# NB-IoT-ideaboard-with-GPS-withnames.net
KiCad netlist of a schematic drawn in EAGLE
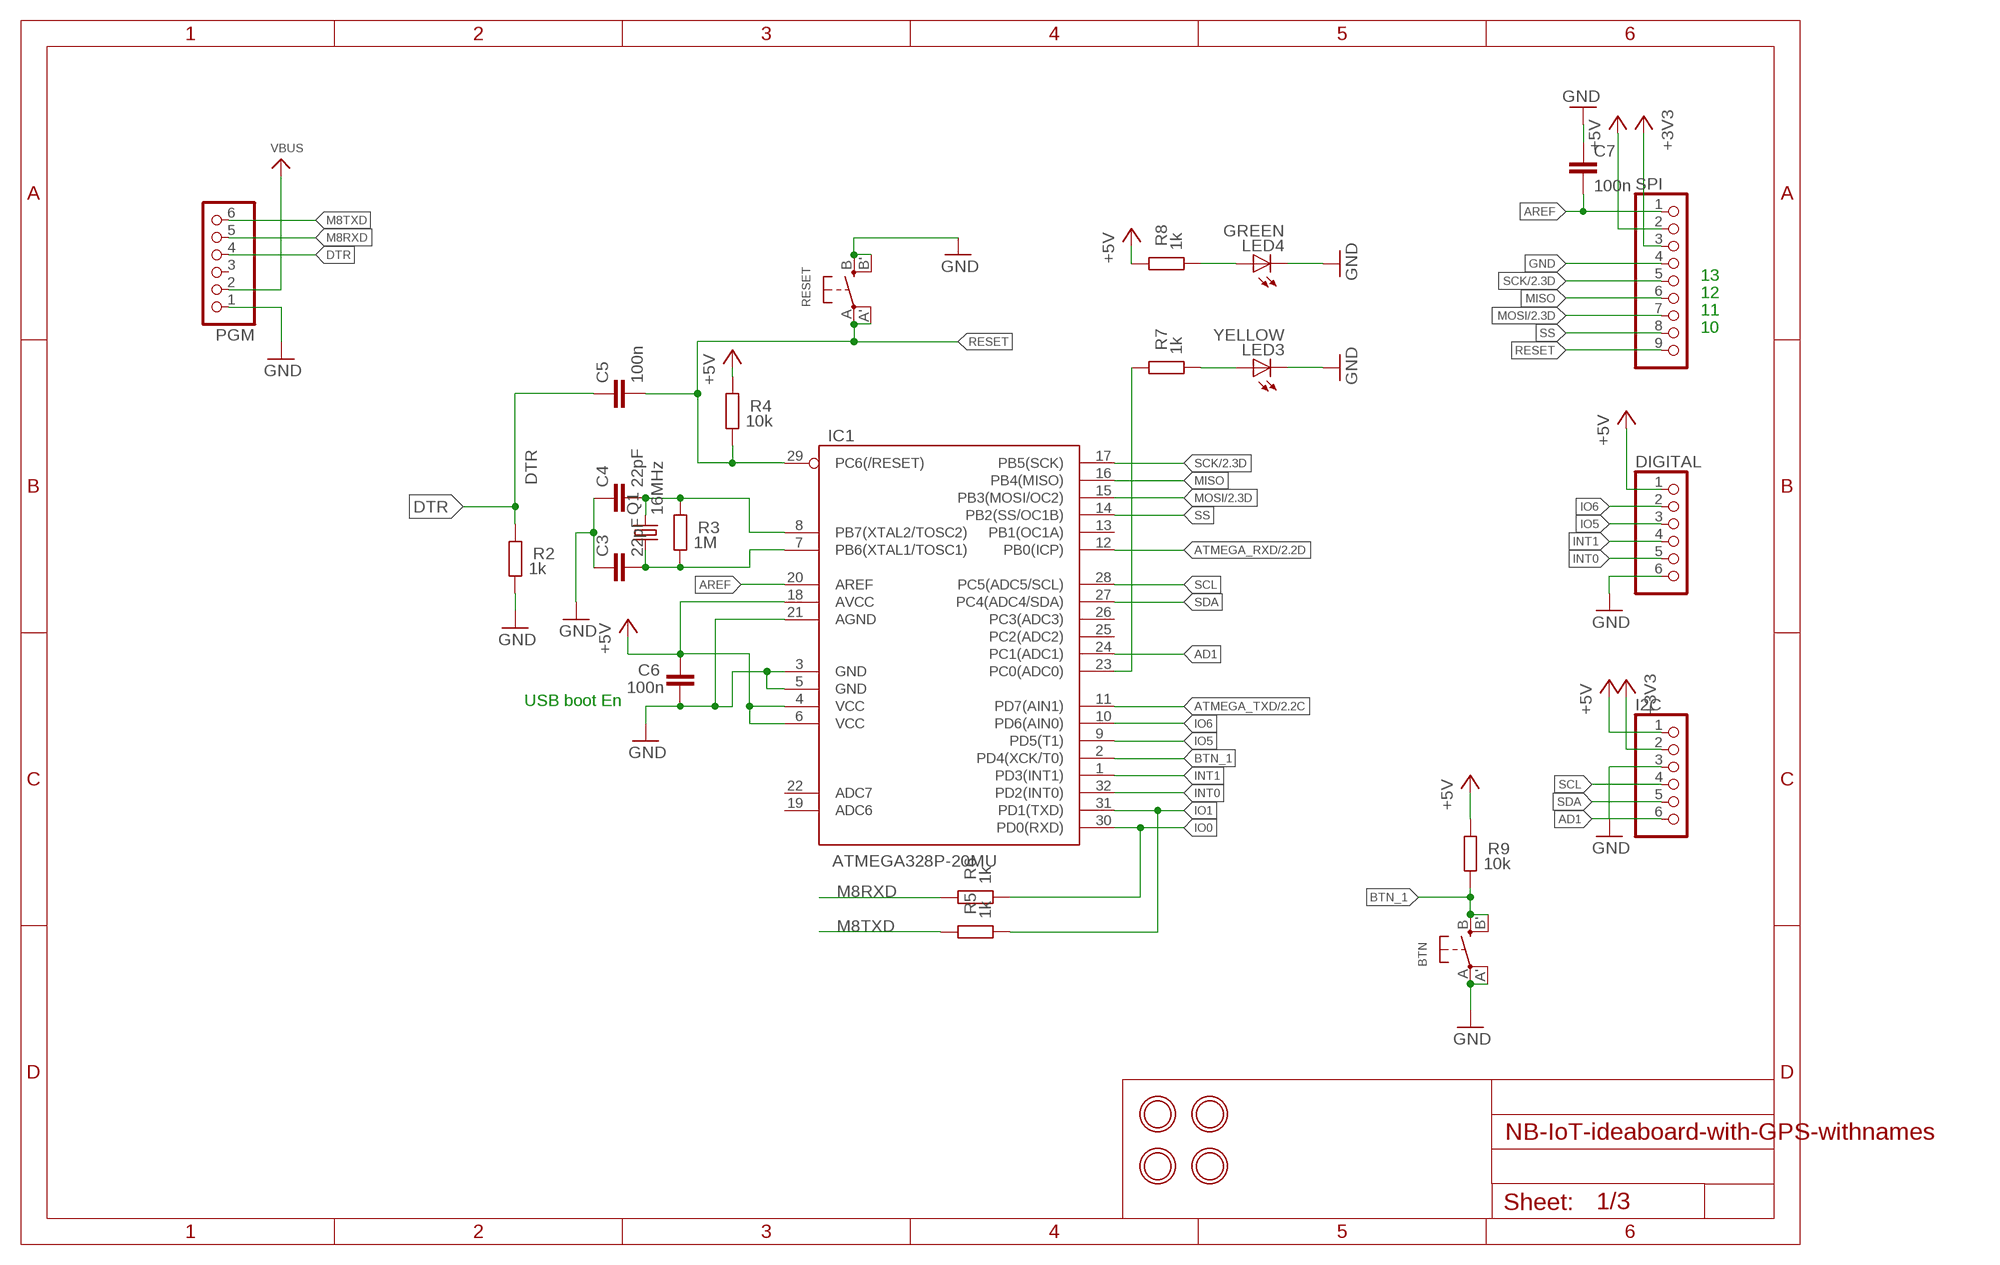
[diagram p0: schematic, sheet 1]
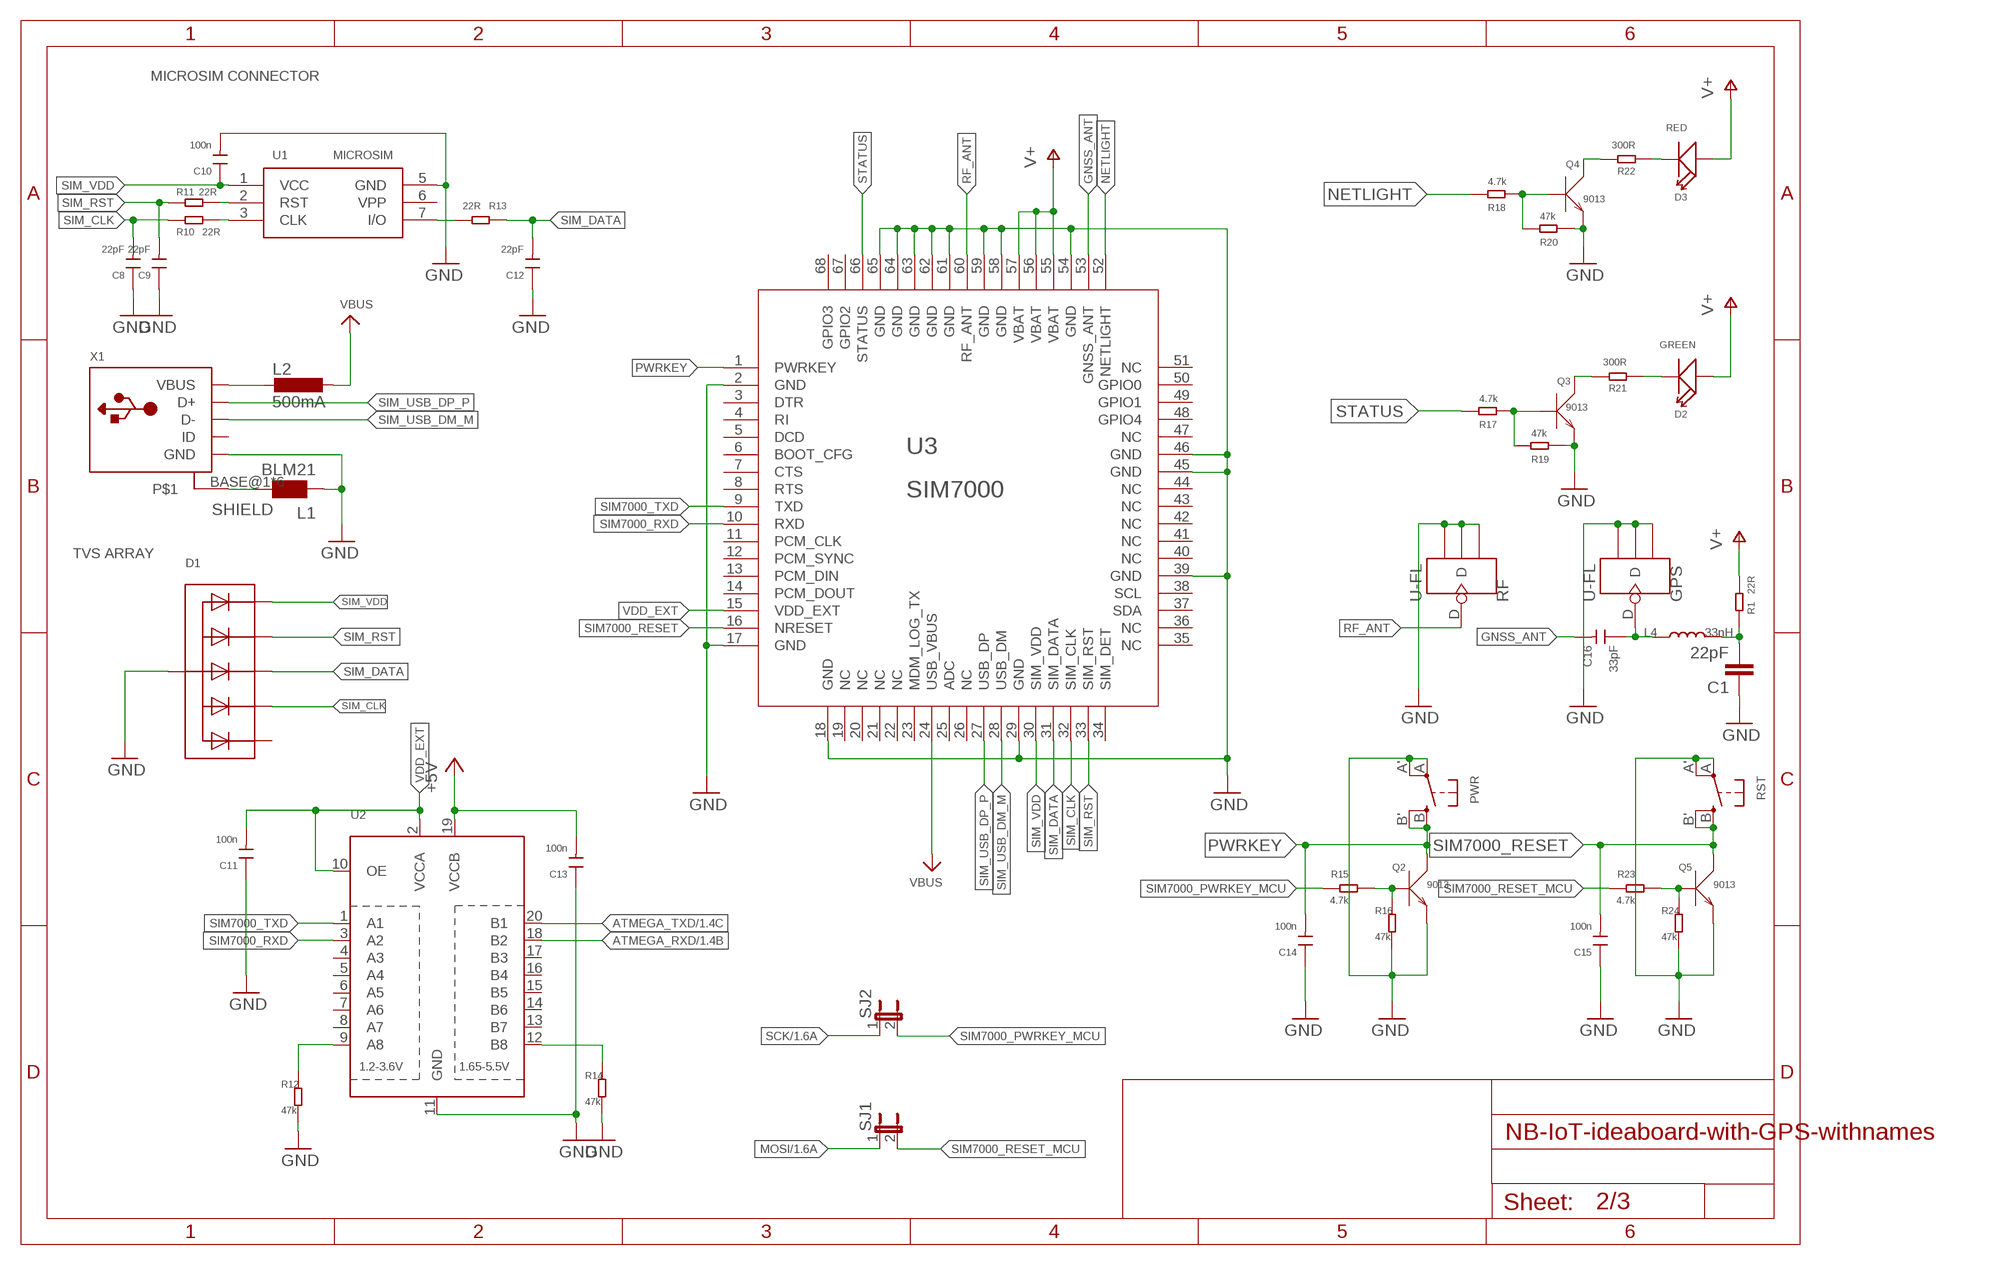
[diagram p1: schematic, sheet 2]
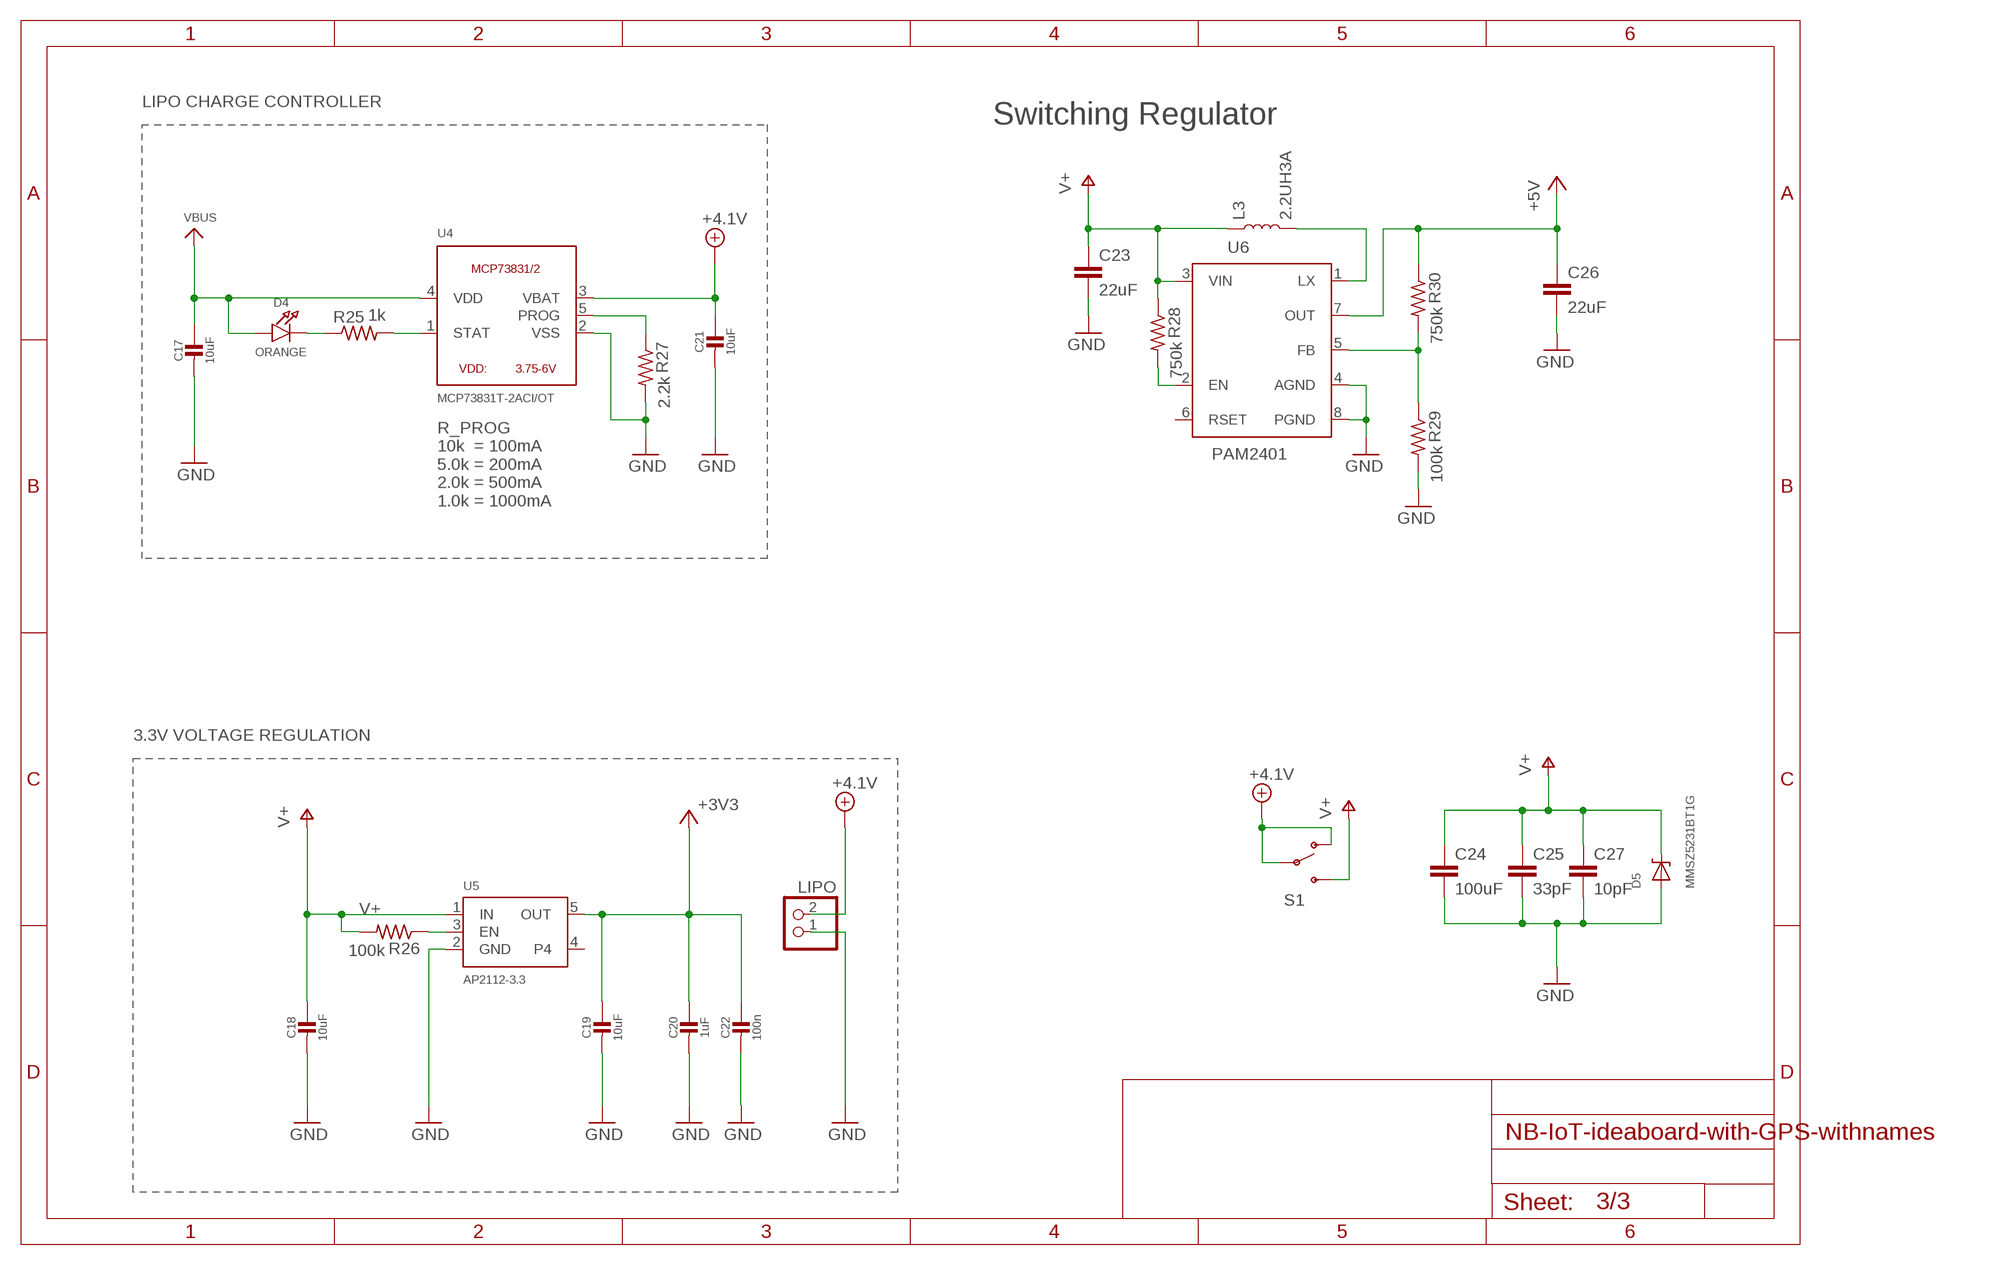
[diagram p2: schematic, sheet 3]

(export (version "E")
  (design (tool "Eeschema 10.0.6"))
  (components
    (comp (ref "C17")
      (value "10uF")
      (footprint "eagle-import:_0805")
      (libsource (lib "eagle-import") (part "CAP_CERAMIC_0805"))
    )
    (comp (ref "C18")
      (value "10uF")
      (footprint "eagle-import:_0805MP")
      (libsource (lib "eagle-import") (part "CAP_CERAMIC_0805MP"))
    )
    (comp (ref "C19")
      (value "10uF")
      (footprint "eagle-import:_0805MP")
      (libsource (lib "eagle-import") (part "CAP_CERAMIC_0805MP"))
    )
    (comp (ref "C20")
      (value "1uF")
      (footprint "eagle-import:_0805MP")
      (libsource (lib "eagle-import") (part "CAP_CERAMIC_0805MP"))
    )
    (comp (ref "C21")
      (value "10uF")
      (footprint "eagle-import:_0805")
      (libsource (lib "eagle-import") (part "CAP_CERAMIC_0805"))
    )
    (comp (ref "C22")
      (value "100n")
      (footprint "eagle-import:_0805MP")
      (libsource (lib "eagle-import") (part "CAP_CERAMIC_0805MP"))
    )
    (comp (ref "C23")
      (value "22uF")
      (footprint "eagle-import:0805")
      (libsource (lib "eagle-import") (part "22UF-0805-6.3V-20%"))
    )
    (comp (ref "C24")
      (value "100uF")
      (footprint "eagle-import:1210")
      (libsource (lib "eagle-import") (part "22UF-1210-16V-20%"))
    )
    (comp (ref "C25")
      (value "33pF")
      (footprint "eagle-import:0805")
      (libsource (lib "eagle-import") (part "22UF-0805-6.3V-20%"))
    )
    (comp (ref "C26")
      (value "22uF")
      (footprint "eagle-import:0805")
      (libsource (lib "eagle-import") (part "22UF-0805-6.3V-20%"))
    )
    (comp (ref "C27")
      (value "10pF")
      (footprint "eagle-import:0805")
      (libsource (lib "eagle-import") (part "22UF-0805-6.3V-20%"))
    )
    (comp (ref "D4")
      (value "ORANGE")
      (footprint "eagle-import:CHIPLED_0805")
      (libsource (lib "eagle-import") (part "LED0805"))
    )
    (comp (ref "D5")
      (value "MMSZ5231BT1G")
      (footprint "eagle-import:SOD-123")
      (libsource (lib "eagle-import") (part "DIODE-ZENERSOD123"))
    )
    (comp (ref "L3")
      (value "2.2UH3A")
      (footprint "eagle-import:INDUCTOR_4X4MM")
      (libsource (lib "eagle-import") (part "INDUCTOR-IFSC1515AHER2R2M01"))
    )
    (comp (ref "LIPO")
      (value "JST_2PIN-SMT")
      (footprint "eagle-import:JST-PH-2-SMT")
      (libsource (lib "eagle-import") (part "JST_2PIN-SMT"))
    )
    (comp (ref "R25")
      (value "1k")
      (footprint "eagle-import:M0805")
      (libsource (lib "eagle-import") (part "R-US_M0805"))
    )
    (comp (ref "R26")
      (value "100k")
      (footprint "eagle-import:M0805")
      (libsource (lib "eagle-import") (part "R-US_M0805"))
    )
    (comp (ref "R27")
      (value "2.2k")
      (footprint "eagle-import:M0805")
      (libsource (lib "eagle-import") (part "R-US_M0805"))
    )
    (comp (ref "R28")
      (value "750k")
      (footprint "eagle-import:M0805")
      (libsource (lib "eagle-import") (part "R-US_M0805"))
    )
    (comp (ref "R29")
      (value "100k")
      (footprint "eagle-import:M0805")
      (libsource (lib "eagle-import") (part "R-US_M0805"))
    )
    (comp (ref "R30")
      (value "750k")
      (footprint "eagle-import:M0805")
      (libsource (lib "eagle-import") (part "R-US_M0805"))
    )
    (comp (ref "S1")
      (value "SWITCH-SPDT-SMD-A")
      (footprint "eagle-import:SWITCH-SPST-SMD-A")
      (libsource (lib "eagle-import") (part "SWITCH-SPDT-SMD-A"))
    )
    (comp (ref "U4")
      (value "MCP73831T-2ACI/OT")
      (footprint "eagle-import:SOT23-5")
      (libsource (lib "eagle-import") (part "MCP73831/2"))
    )
    (comp (ref "U5")
      (value "AP2112-3.3")
      (footprint "eagle-import:SOT23-5")
      (libsource (lib "eagle-import") (part "VREG_SOT23-5"))
    )
    (comp (ref "U6")
      (value "PAM2401")
      (footprint "eagle-import:MSOP8")
      (libsource (lib "eagle-import") (part "PAM2401"))
    )
    (comp (ref "$H1")
      (value "MOUNTINGHOLE3.0THIN")
      (footprint "eagle-import:MOUNTINGHOLE_3.0_PLATEDTHIN")
      (libsource (lib "eagle-import") (part "MOUNTINGHOLE3.0THIN"))
    )
    (comp (ref "$H2")
      (value "MOUNTINGHOLE3.0THIN")
      (footprint "eagle-import:MOUNTINGHOLE_3.0_PLATEDTHIN")
      (libsource (lib "eagle-import") (part "MOUNTINGHOLE3.0THIN"))
    )
    (comp (ref "$H3")
      (value "MOUNTINGHOLE3.0THIN")
      (footprint "eagle-import:MOUNTINGHOLE_3.0_PLATEDTHIN")
      (libsource (lib "eagle-import") (part "MOUNTINGHOLE3.0THIN"))
    )
    (comp (ref "$H4")
      (value "MOUNTINGHOLE3.0THIN")
      (footprint "eagle-import:MOUNTINGHOLE_3.0_PLATEDTHIN")
      (libsource (lib "eagle-import") (part "MOUNTINGHOLE3.0THIN"))
    )
    (comp (ref "BTN")
      (value "SWITCH_TACT_SMT4.6X2.8")
      (footprint "eagle-import:BTN_KMR2_4.6X2.8")
      (libsource (lib "eagle-import") (part "SWITCH_TACT_SMT4.6X2.8"))
    )
    (comp (ref "C3")
      (value "22pF")
      (footprint "eagle-import:C0805")
      (libsource (lib "eagle-import") (part "C-EUC0805"))
    )
    (comp (ref "C4")
      (value "22pF")
      (footprint "eagle-import:C0805")
      (libsource (lib "eagle-import") (part "C-EUC0805"))
    )
    (comp (ref "C5")
      (value "100n")
      (footprint "eagle-import:C0805")
      (libsource (lib "eagle-import") (part "C-EUC0805"))
    )
    (comp (ref "C6")
      (value "100n")
      (footprint "eagle-import:C0805")
      (libsource (lib "eagle-import") (part "C-EUC0805"))
    )
    (comp (ref "C7")
      (value "100n")
      (footprint "eagle-import:C0805")
      (libsource (lib "eagle-import") (part "C-EUC0805"))
    )
    (comp (ref "DIGITAL")
      (value "PINHD-1X6")
      (footprint "eagle-import:1X06")
      (libsource (lib "eagle-import") (part "PINHD-1X6"))
    )
    (comp (ref "I2C")
      (value "PINHD-1X6")
      (footprint "eagle-import:1X06")
      (libsource (lib "eagle-import") (part "PINHD-1X6"))
    )
    (comp (ref "IC1")
      (value "ATMEGA328P-20MU")
      (footprint "eagle-import:TQFP32-08")
      (libsource (lib "eagle-import") (part "MEGA8-AI"))
    )
    (comp (ref "LED3")
      (value "YELLOW")
      (footprint "eagle-import:CHIP-LED0805")
      (libsource (lib "eagle-import") (part "LEDCHIP-LED0805"))
    )
    (comp (ref "LED4")
      (value "GREEN")
      (footprint "eagle-import:CHIP-LED0805")
      (libsource (lib "eagle-import") (part "LEDCHIP-LED0805"))
    )
    (comp (ref "PGM")
      (value "PINHD-1X6")
      (footprint "eagle-import:1X06")
      (libsource (lib "eagle-import") (part "PINHD-1X6"))
    )
    (comp (ref "Q1")
      (value "16MHz")
      (footprint "eagle-import:CTS406")
      (libsource (lib "eagle-import") (part "CRYSTALCTS406"))
    )
    (comp (ref "R2")
      (value "1k")
      (footprint "eagle-import:R0805")
      (libsource (lib "eagle-import") (part "R-EU_R0805"))
    )
    (comp (ref "R3")
      (value "1M")
      (footprint "eagle-import:R0805")
      (libsource (lib "eagle-import") (part "R-EU_R0805"))
    )
    (comp (ref "R4")
      (value "10k")
      (footprint "eagle-import:R0805")
      (libsource (lib "eagle-import") (part "R-EU_R0805"))
    )
    (comp (ref "R5")
      (value "1k")
      (footprint "eagle-import:R0805")
      (libsource (lib "eagle-import") (part "R-EU_R0805"))
    )
    (comp (ref "R6")
      (value "1k")
      (footprint "eagle-import:R0805")
      (libsource (lib "eagle-import") (part "R-EU_R0805"))
    )
    (comp (ref "R7")
      (value "1k")
      (footprint "eagle-import:R0805")
      (libsource (lib "eagle-import") (part "R-EU_R0805"))
    )
    (comp (ref "R8")
      (value "1k")
      (footprint "eagle-import:R0805")
      (libsource (lib "eagle-import") (part "R-EU_R0805"))
    )
    (comp (ref "R9")
      (value "10k")
      (footprint "eagle-import:R0805")
      (libsource (lib "eagle-import") (part "R-EU_R0805"))
    )
    (comp (ref "RESET")
      (value "SWITCH_TACT_SMT4.6X2.8")
      (footprint "eagle-import:BTN_KMR2_4.6X2.8")
      (libsource (lib "eagle-import") (part "SWITCH_TACT_SMT4.6X2.8"))
    )
    (comp (ref "SPI")
      (value "PINHD-1X9")
      (footprint "eagle-import:1X09")
      (libsource (lib "eagle-import") (part "PINHD-1X9"))
    )
    (comp (ref "C1")
      (value "22pF")
      (footprint "eagle-import:C0805")
      (libsource (lib "eagle-import") (part "C-EUC0805"))
    )
    (comp (ref "C8")
      (value "22pF")
      (footprint "eagle-import:0805")
      (libsource (lib "eagle-import") (part "C-0805"))
    )
    (comp (ref "C9")
      (value "22pF")
      (footprint "eagle-import:0805")
      (libsource (lib "eagle-import") (part "C-0805"))
    )
    (comp (ref "C10")
      (value "100n")
      (footprint "eagle-import:0805")
      (libsource (lib "eagle-import") (part "C-0805"))
    )
    (comp (ref "C11")
      (value "100n")
      (footprint "eagle-import:0805")
      (libsource (lib "eagle-import") (part "C-0805"))
    )
    (comp (ref "C12")
      (value "22pF")
      (footprint "eagle-import:0805")
      (libsource (lib "eagle-import") (part "C-0805"))
    )
    (comp (ref "C13")
      (value "100n")
      (footprint "eagle-import:0805")
      (libsource (lib "eagle-import") (part "C-0805"))
    )
    (comp (ref "C14")
      (value "100n")
      (footprint "eagle-import:0805")
      (libsource (lib "eagle-import") (part "C-0805"))
    )
    (comp (ref "C15")
      (value "100n")
      (footprint "eagle-import:0805")
      (libsource (lib "eagle-import") (part "C-0805"))
    )
    (comp (ref "C16")
      (value "33pF")
      (footprint "eagle-import:0805")
      (libsource (lib "eagle-import") (part "C-0805"))
    )
    (comp (ref "D1")
      (value "TVSARRAY_5LANE")
      (footprint "eagle-import:SOT363")
      (libsource (lib "eagle-import") (part "TVSARRAY_5LANE"))
    )
    (comp (ref "D2")
      (value "GREEN")
      (footprint "eagle-import:LED-0805")
      (libsource (lib "eagle-import") (part "LED'0805'"))
    )
    (comp (ref "D3")
      (value "RED")
      (footprint "eagle-import:LED-0805")
      (libsource (lib "eagle-import") (part "LED'0805'"))
    )
    (comp (ref "GPS")
      (value "U-FL")
      (footprint "eagle-import:4P-U-FL")
      (libsource (lib "eagle-import") (part "ANTENNA-U-FL"))
    )
    (comp (ref "L1")
      (value "BLM21")
      (footprint "eagle-import:0805")
      (libsource (lib "eagle-import") (part "WE-CBF_0805"))
    )
    (comp (ref "L2")
      (value "500mA")
      (footprint "eagle-import:L1812")
      (libsource (lib "eagle-import") (part "L-EUL1812"))
    )
    (comp (ref "L4")
      (value "33nH")
      (footprint "eagle-import:L0805")
      (libsource (lib "eagle-import") (part "L0805"))
    )
    (comp (ref "PWR")
      (value "SWITCH_TACT_SMT4.6X2.8")
      (footprint "eagle-import:BTN_KMR2_4.6X2.8")
      (libsource (lib "eagle-import") (part "SWITCH_TACT_SMT4.6X2.8"))
    )
    (comp (ref "Q2")
      (value "9013")
      (footprint "eagle-import:SOT23")
      (libsource (lib "eagle-import") (part "TRANSISTOR-NPN-SOT23"))
    )
    (comp (ref "Q3")
      (value "9013")
      (footprint "eagle-import:SOT23")
      (libsource (lib "eagle-import") (part "TRANSISTOR-NPN-SOT23"))
    )
    (comp (ref "Q4")
      (value "9013")
      (footprint "eagle-import:SOT23")
      (libsource (lib "eagle-import") (part "TRANSISTOR-NPN-SOT23"))
    )
    (comp (ref "Q5")
      (value "9013")
      (footprint "eagle-import:SOT23")
      (libsource (lib "eagle-import") (part "TRANSISTOR-NPN-SOT23"))
    )
    (comp (ref "R1")
      (value "22R")
      (footprint "eagle-import:0805")
      (libsource (lib "eagle-import") (part "R-0805"))
    )
    (comp (ref "R10")
      (value "22R")
      (footprint "eagle-import:0805")
      (libsource (lib "eagle-import") (part "R-0805"))
    )
    (comp (ref "R11")
      (value "22R")
      (footprint "eagle-import:0805")
      (libsource (lib "eagle-import") (part "R-0805"))
    )
    (comp (ref "R12")
      (value "47k")
      (footprint "eagle-import:0805")
      (libsource (lib "eagle-import") (part "R-0805"))
    )
    (comp (ref "R13")
      (value "22R")
      (footprint "eagle-import:0805")
      (libsource (lib "eagle-import") (part "R-0805"))
    )
    (comp (ref "R14")
      (value "47k")
      (footprint "eagle-import:0805")
      (libsource (lib "eagle-import") (part "R-0805"))
    )
    (comp (ref "R15")
      (value "4.7k")
      (footprint "eagle-import:0805")
      (libsource (lib "eagle-import") (part "R-0805"))
    )
    (comp (ref "R16")
      (value "47k")
      (footprint "eagle-import:0805")
      (libsource (lib "eagle-import") (part "R-0805"))
    )
    (comp (ref "R17")
      (value "4.7k")
      (footprint "eagle-import:0805")
      (libsource (lib "eagle-import") (part "R-0805"))
    )
    (comp (ref "R18")
      (value "4.7k")
      (footprint "eagle-import:0805")
      (libsource (lib "eagle-import") (part "R-0805"))
    )
    (comp (ref "R19")
      (value "47k")
      (footprint "eagle-import:0805")
      (libsource (lib "eagle-import") (part "R-0805"))
    )
    (comp (ref "R20")
      (value "47k")
      (footprint "eagle-import:0805")
      (libsource (lib "eagle-import") (part "R-0805"))
    )
    (comp (ref "R21")
      (value "300R")
      (footprint "eagle-import:0805")
      (libsource (lib "eagle-import") (part "R-0805"))
    )
    (comp (ref "R22")
      (value "300R")
      (footprint "eagle-import:0805")
      (libsource (lib "eagle-import") (part "R-0805"))
    )
    (comp (ref "R23")
      (value "4.7k")
      (footprint "eagle-import:0805")
      (libsource (lib "eagle-import") (part "R-0805"))
    )
    (comp (ref "R24")
      (value "47k")
      (footprint "eagle-import:0805")
      (libsource (lib "eagle-import") (part "R-0805"))
    )
    (comp (ref "RF")
      (value "U-FL")
      (footprint "eagle-import:4P-U-FL")
      (libsource (lib "eagle-import") (part "ANTENNA-U-FL"))
    )
    (comp (ref "RST")
      (value "SWITCH_TACT_SMT4.6X2.8")
      (footprint "eagle-import:BTN_KMR2_4.6X2.8")
      (libsource (lib "eagle-import") (part "SWITCH_TACT_SMT4.6X2.8"))
    )
    (comp (ref "SJ1")
      (value "SPARKFUN-PASSIVES_JUMPER-PTH-2-NC")
      (footprint "eagle-import:SPARKFUN-PASSIVES_PTH-JUMPER-NC_BOTTOM_NO_SILK")
      (libsource (lib "eagle-import") (part "SPARKFUN-PASSIVES_JUMPER-PTH-2-NC"))
    )
    (comp (ref "SJ2")
      (value "SPARKFUN-PASSIVES_JUMPER-PTH-2-NC")
      (footprint "eagle-import:SPARKFUN-PASSIVES_PTH-JUMPER-NC_BOTTOM_NO_SILK")
      (libsource (lib "eagle-import") (part "SPARKFUN-PASSIVES_JUMPER-PTH-2-NC"))
    )
    (comp (ref "U1")
      (value "MICROSIM")
      (footprint "eagle-import:MICROSIM")
      (libsource (lib "eagle-import") (part "MICROSIM"))
    )
    (comp (ref "U2")
      (value "TXB0108PWR")
      (footprint "eagle-import:TSSOP20")
      (libsource (lib "eagle-import") (part "TXB0108PWR"))
    )
    (comp (ref "U3")
      (value "SIM7000")
      (footprint "eagle-import:SIM7000")
      (libsource (lib "eagle-import") (part "SIM7000"))
    )
    (comp (ref "X1")
      (value "USB_MICRO_20329_V2")
      (footprint "eagle-import:4UCONN_20329_V2")
      (libsource (lib "eagle-import") (part "USB_MICRO_20329_V2"))
    )
  )
  (nets
    (net (code "1") (name "+3V3") (class "Default")
      (node (ref "C19") (pin "1") (pinfunction "1_1") (pintype "passive"))
      (node (ref "C20") (pin "1") (pinfunction "1_1") (pintype "passive"))
      (node (ref "C22") (pin "1") (pinfunction "1_1") (pintype "passive"))
      (node (ref "I2C") (pin "2") (pinfunction "2_2") (pintype "passive"))
      (node (ref "SPI") (pin "3") (pinfunction "3_3") (pintype "passive"))
      (node (ref "U5") (pin "5") (pinfunction "OUT_5") (pintype "power_in"))
    )
    (net (code "2") (name "+4.1V") (class "Default")
      (node (ref "C21") (pin "1") (pinfunction "1_1") (pintype "passive"))
      (node (ref "LIPO") (pin "2") (pinfunction "1_2") (pintype "passive"))
      (node (ref "S1") (pin "1") (pinfunction "O_1") (pintype "passive"))
      (node (ref "S1") (pin "2") (pinfunction "P_2") (pintype "passive"))
      (node (ref "U4") (pin "3") (pinfunction "VBAT_3") (pintype "power_in"))
    )
    (net (code "3") (name "+5V") (class "Default")
      (node (ref "C13") (pin "2") (pinfunction "2_2") (pintype "passive"))
      (node (ref "C26") (pin "1") (pinfunction "1_1") (pintype "passive"))
      (node (ref "C6") (pin "2") (pinfunction "2_2") (pintype "passive"))
      (node (ref "DIGITAL") (pin "1") (pinfunction "1_1") (pintype "passive"))
      (node (ref "I2C") (pin "1") (pinfunction "1_1") (pintype "passive"))
      (node (ref "IC1") (pin "18") (pinfunction "AVCC_18") (pintype "bidirectional"))
      (node (ref "IC1") (pin "4") (pinfunction "VCC_4") (pintype "bidirectional"))
      (node (ref "IC1") (pin "6") (pinfunction "VCC_6") (pintype "bidirectional"))
      (node (ref "R30") (pin "1") (pinfunction "1_1") (pintype "passive"))
      (node (ref "R4") (pin "2") (pinfunction "2_2") (pintype "passive"))
      (node (ref "R8") (pin "2") (pinfunction "2_2") (pintype "passive"))
      (node (ref "R9") (pin "2") (pinfunction "2_2") (pintype "passive"))
      (node (ref "SPI") (pin "2") (pinfunction "2_2") (pintype "passive"))
      (node (ref "U2") (pin "19") (pinfunction "VCCB_19") (pintype "bidirectional"))
      (node (ref "U6") (pin "7") (pinfunction "OUT_7") (pintype "bidirectional"))
    )
    (net (code "4") (name "AD1") (class "Default")
      (node (ref "I2C") (pin "6") (pinfunction "6_6") (pintype "passive"))
      (node (ref "IC1") (pin "24") (pinfunction "PC1(ADC1)_24") (pintype "bidirectional"))
    )
    (net (code "5") (name "AREF") (class "Default")
      (node (ref "C7") (pin "2") (pinfunction "2_2") (pintype "passive"))
      (node (ref "IC1") (pin "20") (pinfunction "AREF_20") (pintype "bidirectional"))
      (node (ref "SPI") (pin "1") (pinfunction "1_1") (pintype "passive"))
    )
    (net (code "6") (name "ATMEGA_RXD") (class "Default")
      (node (ref "IC1") (pin "12") (pinfunction "PB0(ICP)_12") (pintype "bidirectional"))
      (node (ref "U2") (pin "18") (pinfunction "B2_18") (pintype "bidirectional"))
    )
    (net (code "7") (name "ATMEGA_TXD") (class "Default")
      (node (ref "IC1") (pin "11") (pinfunction "PD7(AIN1)_11") (pintype "bidirectional"))
      (node (ref "U2") (pin "20") (pinfunction "B1_20") (pintype "bidirectional"))
    )
    (net (code "8") (name "BTN_1") (class "Default")
      (node (ref "BTN") (pin "B") (pinfunction "S_B") (pintype "passive"))
      (node (ref "BTN") (pin "B'") (pinfunction "S1_B'") (pintype "passive"))
      (node (ref "IC1") (pin "2") (pinfunction "PD4(XCK/T0)_2") (pintype "bidirectional"))
      (node (ref "R9") (pin "1") (pinfunction "1_1") (pintype "passive"))
    )
    (net (code "9") (name "DTR") (class "Default")
      (node (ref "C5") (pin "1") (pinfunction "1_1") (pintype "passive"))
      (node (ref "PGM") (pin "4") (pinfunction "4_4") (pintype "passive"))
      (node (ref "R2") (pin "2") (pinfunction "2_2") (pintype "passive"))
    )
    (net (code "10") (name "GND") (class "Default")
      (node (ref "BTN") (pin "A") (pinfunction "P_A") (pintype "passive"))
      (node (ref "BTN") (pin "A'") (pinfunction "P1_A'") (pintype "passive"))
      (node (ref "C1") (pin "1") (pinfunction "1_1") (pintype "passive"))
      (node (ref "C10") (pin "2") (pinfunction "2_2") (pintype "passive"))
      (node (ref "C11") (pin "1") (pinfunction "1_1") (pintype "passive"))
      (node (ref "C12") (pin "1") (pinfunction "1_1") (pintype "passive"))
      (node (ref "C13") (pin "1") (pinfunction "1_1") (pintype "passive"))
      (node (ref "C14") (pin "1") (pinfunction "1_1") (pintype "passive"))
      (node (ref "C15") (pin "1") (pinfunction "1_1") (pintype "passive"))
      (node (ref "C17") (pin "2") (pinfunction "2_2") (pintype "passive"))
      (node (ref "C18") (pin "2") (pinfunction "2_2") (pintype "passive"))
      (node (ref "C19") (pin "2") (pinfunction "2_2") (pintype "passive"))
      (node (ref "C20") (pin "2") (pinfunction "2_2") (pintype "passive"))
      (node (ref "C21") (pin "2") (pinfunction "2_2") (pintype "passive"))
      (node (ref "C22") (pin "2") (pinfunction "2_2") (pintype "passive"))
      (node (ref "C23") (pin "2") (pinfunction "2_2") (pintype "passive"))
      (node (ref "C24") (pin "2") (pinfunction "2_2") (pintype "passive"))
      (node (ref "C25") (pin "2") (pinfunction "2_2") (pintype "passive"))
      (node (ref "C26") (pin "2") (pinfunction "2_2") (pintype "passive"))
      (node (ref "C27") (pin "2") (pinfunction "2_2") (pintype "passive"))
      (node (ref "C3") (pin "1") (pinfunction "1_1") (pintype "passive"))
      (node (ref "C4") (pin "1") (pinfunction "1_1") (pintype "passive"))
      (node (ref "C6") (pin "1") (pinfunction "1_1") (pintype "passive"))
      (node (ref "C7") (pin "1") (pinfunction "1_1") (pintype "passive"))
      (node (ref "C8") (pin "1") (pinfunction "1_1") (pintype "passive"))
      (node (ref "C9") (pin "1") (pinfunction "1_1") (pintype "passive"))
      (node (ref "D1") (pin "2") (pinfunction "A_2") (pintype "passive"))
      (node (ref "D5") (pin "A") (pinfunction "A_A") (pintype "passive"))
      (node (ref "DIGITAL") (pin "6") (pinfunction "6_6") (pintype "passive"))
      (node (ref "GPS") (pin "GND1") (pinfunction "GND1_GND1") (pintype "bidirectional"))
      (node (ref "GPS") (pin "GND2") (pinfunction "GND2_GND2") (pintype "bidirectional"))
      (node (ref "GPS") (pin "GND3") (pinfunction "GND3_GND3") (pintype "bidirectional"))
      (node (ref "I2C") (pin "3") (pinfunction "3_3") (pintype "passive"))
      (node (ref "IC1") (pin "21") (pinfunction "AGND_21") (pintype "bidirectional"))
      (node (ref "IC1") (pin "3") (pinfunction "GND_3") (pintype "bidirectional"))
      (node (ref "IC1") (pin "5") (pinfunction "GND_5") (pintype "bidirectional"))
      (node (ref "L1") (pin "1") (pinfunction "1_1") (pintype "passive"))
      (node (ref "LED3") (pin "C") (pinfunction "C_C") (pintype "passive"))
      (node (ref "LED4") (pin "C") (pinfunction "C_C") (pintype "passive"))
      (node (ref "LIPO") (pin "1") (pinfunction "2_1") (pintype "passive"))
      (node (ref "PGM") (pin "1") (pinfunction "1_1") (pintype "passive"))
      (node (ref "PWR") (pin "A") (pinfunction "P_A") (pintype "passive"))
      (node (ref "PWR") (pin "A'") (pinfunction "P1_A'") (pintype "passive"))
      (node (ref "Q2") (pin "2") (pinfunction "E_2") (pintype "passive"))
      (node (ref "Q3") (pin "2") (pinfunction "E_2") (pintype "passive"))
      (node (ref "Q4") (pin "2") (pinfunction "E_2") (pintype "passive"))
      (node (ref "Q5") (pin "2") (pinfunction "E_2") (pintype "passive"))
      (node (ref "R12") (pin "2") (pinfunction "2_2") (pintype "passive"))
      (node (ref "R14") (pin "2") (pinfunction "2_2") (pintype "passive"))
      (node (ref "R16") (pin "2") (pinfunction "2_2") (pintype "passive"))
      (node (ref "R19") (pin "2") (pinfunction "2_2") (pintype "passive"))
      (node (ref "R2") (pin "1") (pinfunction "1_1") (pintype "passive"))
      (node (ref "R20") (pin "2") (pinfunction "2_2") (pintype "passive"))
      (node (ref "R24") (pin "2") (pinfunction "2_2") (pintype "passive"))
      (node (ref "R27") (pin "2") (pinfunction "2_2") (pintype "passive"))
      (node (ref "R29") (pin "2") (pinfunction "2_2") (pintype "passive"))
      (node (ref "RESET") (pin "B") (pinfunction "S_B") (pintype "passive"))
      (node (ref "RESET") (pin "B'") (pinfunction "S1_B'") (pintype "passive"))
      (node (ref "RF") (pin "GND1") (pinfunction "GND1_GND1") (pintype "bidirectional"))
      (node (ref "RF") (pin "GND2") (pinfunction "GND2_GND2") (pintype "bidirectional"))
      (node (ref "RF") (pin "GND3") (pinfunction "GND3_GND3") (pintype "bidirectional"))
      (node (ref "RST") (pin "A") (pinfunction "P_A") (pintype "passive"))
      (node (ref "RST") (pin "A'") (pinfunction "P1_A'") (pintype "passive"))
      (node (ref "SPI") (pin "4") (pinfunction "4_4") (pintype "passive"))
      (node (ref "U1") (pin "5") (pinfunction "GND_5") (pintype "bidirectional"))
      (node (ref "U2") (pin "11") (pinfunction "GND_11") (pintype "bidirectional"))
      (node (ref "U3") (pin "17") (pinfunction "GND_17") (pintype "power_in"))
      (node (ref "U3") (pin "18") (pinfunction "GND_18") (pintype "power_in"))
      (node (ref "U3") (pin "2") (pinfunction "GND_2") (pintype "power_in"))
      (node (ref "U3") (pin "29") (pinfunction "GND_29") (pintype "power_in"))
      (node (ref "U3") (pin "39") (pinfunction "GND_39") (pintype "power_in"))
      (node (ref "U3") (pin "45") (pinfunction "GND_45") (pintype "power_in"))
      (node (ref "U3") (pin "46") (pinfunction "GND_46") (pintype "power_in"))
      (node (ref "U3") (pin "54") (pinfunction "GND_54") (pintype "power_in"))
      (node (ref "U3") (pin "58") (pinfunction "GND_58") (pintype "output"))
      (node (ref "U3") (pin "59") (pinfunction "GND_59") (pintype "bidirectional"))
      (node (ref "U3") (pin "61") (pinfunction "GND_61") (pintype "input"))
      (node (ref "U3") (pin "62") (pinfunction "GND_62") (pintype "output"))
      (node (ref "U3") (pin "63") (pinfunction "GND_63") (pintype "output"))
      (node (ref "U3") (pin "64") (pinfunction "GND_64") (pintype "input"))
      (node (ref "U3") (pin "65") (pinfunction "GND_65") (pintype "bidirectional"))
      (node (ref "U4") (pin "2") (pinfunction "VSS_2") (pintype "power_in"))
      (node (ref "U5") (pin "2") (pinfunction "GND_2") (pintype "power_in"))
      (node (ref "U6") (pin "4") (pinfunction "AGND_4") (pintype "bidirectional"))
      (node (ref "U6") (pin "8") (pinfunction "PGND_8") (pintype "bidirectional"))
      (node (ref "X1") (pin "GND") (pinfunction "GND_GND") (pintype "power_in"))
    )
    (net (code "11") (name "GNSS_ANT") (class "Default")
      (node (ref "C16") (pin "2") (pinfunction "2_2") (pintype "passive"))
      (node (ref "U3") (pin "53") (pinfunction "GNSS_ANT_53") (pintype "power_in"))
    )
    (net (code "12") (name "GPIO2") (class "Default")
      (node (ref "U3") (pin "67") (pinfunction "GPIO2_67") (pintype "power_in"))
    )
    (net (code "13") (name "GPIO3") (class "Default")
      (node (ref "U3") (pin "68") (pinfunction "GPIO3_68") (pintype "power_in"))
    )
    (net (code "14") (name "INT0") (class "Default")
      (node (ref "DIGITAL") (pin "5") (pinfunction "5_5") (pintype "passive"))
      (node (ref "IC1") (pin "32") (pinfunction "PD2(INT0)_32") (pintype "bidirectional"))
    )
    (net (code "15") (name "INT1") (class "Default")
      (node (ref "DIGITAL") (pin "4") (pinfunction "4_4") (pintype "passive"))
      (node (ref "IC1") (pin "1") (pinfunction "PD3(INT1)_1") (pintype "bidirectional"))
    )
    (net (code "16") (name "IO0") (class "Default")
      (node (ref "IC1") (pin "30") (pinfunction "PD0(RXD)_30") (pintype "bidirectional"))
      (node (ref "R6") (pin "1") (pinfunction "1_1") (pintype "passive"))
    )
    (net (code "17") (name "IO1") (class "Default")
      (node (ref "IC1") (pin "31") (pinfunction "PD1(TXD)_31") (pintype "bidirectional"))
      (node (ref "R5") (pin "1") (pinfunction "1_1") (pintype "passive"))
    )
    (net (code "18") (name "IO5") (class "Default")
      (node (ref "DIGITAL") (pin "3") (pinfunction "3_3") (pintype "passive"))
      (node (ref "IC1") (pin "9") (pinfunction "PD5(T1)_9") (pintype "bidirectional"))
    )
    (net (code "19") (name "IO6") (class "Default")
      (node (ref "DIGITAL") (pin "2") (pinfunction "2_2") (pintype "passive"))
      (node (ref "IC1") (pin "10") (pinfunction "PD6(AIN0)_10") (pintype "bidirectional"))
    )
    (net (code "20") (name "M8RXD") (class "Default")
      (node (ref "PGM") (pin "5") (pinfunction "5_5") (pintype "passive"))
      (node (ref "R6") (pin "2") (pinfunction "2_2") (pintype "passive"))
    )
    (net (code "21") (name "M8TXD") (class "Default")
      (node (ref "PGM") (pin "6") (pinfunction "6_6") (pintype "passive"))
      (node (ref "R5") (pin "2") (pinfunction "2_2") (pintype "passive"))
    )
    (net (code "22") (name "MISO") (class "Default")
      (node (ref "IC1") (pin "16") (pinfunction "PB4(MISO)_16") (pintype "bidirectional"))
      (node (ref "SPI") (pin "6") (pinfunction "6_6") (pintype "passive"))
    )
    (net (code "23") (name "MOSI") (class "Default")
      (node (ref "IC1") (pin "15") (pinfunction "PB3(MOSI/OC2)_15") (pintype "bidirectional"))
      (node (ref "SJ1") (pin "1") (pinfunction "1_1") (pintype "passive"))
      (node (ref "SPI") (pin "7") (pinfunction "7_7") (pintype "passive"))
    )
    (net (code "24") (name "NETLIGHT") (class "Default")
      (node (ref "R18") (pin "1") (pinfunction "1_1") (pintype "passive"))
      (node (ref "U3") (pin "52") (pinfunction "NETLIGHT_52") (pintype "power_in"))
    )
    (net (code "25") (name "Net-(C1-Pad2)") (class "Default")
      (node (ref "C1") (pin "2") (pinfunction "2_2") (pintype "passive"))
      (node (ref "L4") (pin "2") (pinfunction "2_2") (pintype "passive"))
      (node (ref "R1") (pin "2") (pinfunction "2_2") (pintype "passive"))
    )
    (net (code "26") (name "Net-(C16-Pad1)") (class "Default")
      (node (ref "C16") (pin "1") (pinfunction "1_1") (pintype "passive"))
      (node (ref "GPS") (pin "D") (pinfunction "D_D") (pintype "bidirectional"))
      (node (ref "L4") (pin "1") (pinfunction "1_1") (pintype "passive"))
    )
    (net (code "27") (name "Net-(D2-Pad-)") (class "Default")
      (node (ref "D2") (pin "-") (pinfunction "-_-") (pintype "passive"))
      (node (ref "R21") (pin "1") (pinfunction "1_1") (pintype "passive"))
    )
    (net (code "28") (name "Net-(D3-Pad-)") (class "Default")
      (node (ref "D3") (pin "-") (pinfunction "-_-") (pintype "passive"))
      (node (ref "R22") (pin "1") (pinfunction "1_1") (pintype "passive"))
    )
    (net (code "29") (name "Net-(D4-PadC)") (class "Default")
      (node (ref "D4") (pin "C") (pinfunction "C_C") (pintype "passive"))
      (node (ref "R25") (pin "1") (pinfunction "1_1") (pintype "passive"))
    )
    (net (code "30") (name "Net-(IC1-PB6(XTAL1{slash}TOSC1))") (class "Default")
      (node (ref "C3") (pin "2") (pinfunction "2_2") (pintype "passive"))
      (node (ref "IC1") (pin "7") (pinfunction "PB6(XTAL1/TOSC1)_7") (pintype "bidirectional"))
      (node (ref "Q1") (pin "1") (pinfunction "1_1") (pintype "passive"))
      (node (ref "R3") (pin "1") (pinfunction "1_1") (pintype "passive"))
    )
    (net (code "31") (name "Net-(IC1-PB7(XTAL2{slash}TOSC2))") (class "Default")
      (node (ref "C4") (pin "2") (pinfunction "2_2") (pintype "passive"))
      (node (ref "IC1") (pin "8") (pinfunction "PB7(XTAL2/TOSC2)_8") (pintype "bidirectional"))
      (node (ref "Q1") (pin "3") (pinfunction "2_3") (pintype "passive"))
      (node (ref "R3") (pin "2") (pinfunction "2_2") (pintype "passive"))
    )
    (net (code "32") (name "Net-(IC1-PC0(ADC0))") (class "Default")
      (node (ref "IC1") (pin "23") (pinfunction "PC0(ADC0)_23") (pintype "bidirectional"))
      (node (ref "R7") (pin "2") (pinfunction "2_2") (pintype "passive"))
    )
    (net (code "33") (name "Net-(L2-Pad2)") (class "Default")
      (node (ref "L2") (pin "2") (pinfunction "2_2") (pintype "passive"))
      (node (ref "X1") (pin "VBUS") (pinfunction "VBUS_VBUS") (pintype "power_in"))
    )
    (net (code "34") (name "Net-(L3-2)") (class "Default")
      (node (ref "L3") (pin "P$2") (pinfunction "2_P$2") (pintype "passive"))
      (node (ref "U6") (pin "1") (pinfunction "LX_1") (pintype "bidirectional"))
    )
    (net (code "35") (name "Net-(LED3-PadA)") (class "Default")
      (node (ref "LED3") (pin "A") (pinfunction "A_A") (pintype "passive"))
      (node (ref "R7") (pin "1") (pinfunction "1_1") (pintype "passive"))
    )
    (net (code "36") (name "Net-(LED4-PadA)") (class "Default")
      (node (ref "LED4") (pin "A") (pinfunction "A_A") (pintype "passive"))
      (node (ref "R8") (pin "1") (pinfunction "1_1") (pintype "passive"))
    )
    (net (code "37") (name "Net-(Q2-B)") (class "Default")
      (node (ref "Q2") (pin "1") (pinfunction "B_1") (pintype "passive"))
      (node (ref "R15") (pin "2") (pinfunction "2_2") (pintype "passive"))
      (node (ref "R16") (pin "1") (pinfunction "1_1") (pintype "passive"))
    )
    (net (code "38") (name "Net-(Q3-B)") (class "Default")
      (node (ref "Q3") (pin "1") (pinfunction "B_1") (pintype "passive"))
      (node (ref "R17") (pin "2") (pinfunction "2_2") (pintype "passive"))
      (node (ref "R19") (pin "1") (pinfunction "1_1") (pintype "passive"))
    )
    (net (code "39") (name "Net-(Q3-C)") (class "Default")
      (node (ref "Q3") (pin "3") (pinfunction "C_3") (pintype "passive"))
      (node (ref "R21") (pin "2") (pinfunction "2_2") (pintype "passive"))
    )
    (net (code "40") (name "Net-(Q4-B)") (class "Default")
      (node (ref "Q4") (pin "1") (pinfunction "B_1") (pintype "passive"))
      (node (ref "R18") (pin "2") (pinfunction "2_2") (pintype "passive"))
      (node (ref "R20") (pin "1") (pinfunction "1_1") (pintype "passive"))
    )
    (net (code "41") (name "Net-(Q4-C)") (class "Default")
      (node (ref "Q4") (pin "3") (pinfunction "C_3") (pintype "passive"))
      (node (ref "R22") (pin "2") (pinfunction "2_2") (pintype "passive"))
    )
    (net (code "42") (name "Net-(Q5-B)") (class "Default")
      (node (ref "Q5") (pin "1") (pinfunction "B_1") (pintype "passive"))
      (node (ref "R23") (pin "2") (pinfunction "2_2") (pintype "passive"))
      (node (ref "R24") (pin "1") (pinfunction "1_1") (pintype "passive"))
    )
    (net (code "43") (name "Net-(U1-CLK)") (class "Default")
      (node (ref "R10") (pin "1") (pinfunction "1_1") (pintype "passive"))
      (node (ref "U1") (pin "3") (pinfunction "CLK_3") (pintype "bidirectional"))
    )
    (net (code "44") (name "Net-(U1-I{slash}O)") (class "Default")
      (node (ref "R13") (pin "2") (pinfunction "2_2") (pintype "passive"))
      (node (ref "U1") (pin "7") (pinfunction "I/O_7") (pintype "bidirectional"))
    )
    (net (code "45") (name "Net-(U1-RST)") (class "Default")
      (node (ref "R11") (pin "1") (pinfunction "1_1") (pintype "passive"))
      (node (ref "U1") (pin "2") (pinfunction "RST_2") (pintype "bidirectional"))
    )
    (net (code "46") (name "Net-(U2-A8)") (class "Default")
      (node (ref "R12") (pin "1") (pinfunction "1_1") (pintype "passive"))
      (node (ref "U2") (pin "9") (pinfunction "A8_9") (pintype "bidirectional"))
    )
    (net (code "47") (name "Net-(U2-B8)") (class "Default")
      (node (ref "R14") (pin "1") (pinfunction "1_1") (pintype "passive"))
      (node (ref "U2") (pin "12") (pinfunction "B8_12") (pintype "bidirectional"))
    )
    (net (code "48") (name "Net-(U4-PROG)") (class "Default")
      (node (ref "R27") (pin "1") (pinfunction "1_1") (pintype "passive"))
      (node (ref "U4") (pin "5") (pinfunction "PROG_5") (pintype "input"))
    )
    (net (code "49") (name "Net-(U4-STAT)") (class "Default")
      (node (ref "R25") (pin "2") (pinfunction "2_2") (pintype "passive"))
      (node (ref "U4") (pin "1") (pinfunction "STAT_1") (pintype "output"))
    )
    (net (code "50") (name "Net-(U5-EN)") (class "Default")
      (node (ref "R26") (pin "1") (pinfunction "1_1") (pintype "passive"))
      (node (ref "U5") (pin "3") (pinfunction "EN_3") (pintype "input"))
    )
    (net (code "51") (name "Net-(U6-EN)") (class "Default")
      (node (ref "R28") (pin "2") (pinfunction "2_2") (pintype "passive"))
      (node (ref "U6") (pin "2") (pinfunction "EN_2") (pintype "bidirectional"))
    )
    (net (code "52") (name "Net-(U6-FB)") (class "Default")
      (node (ref "R29") (pin "1") (pinfunction "1_1") (pintype "passive"))
      (node (ref "R30") (pin "2") (pinfunction "2_2") (pintype "passive"))
      (node (ref "U6") (pin "5") (pinfunction "FB_5") (pintype "bidirectional"))
    )
    (net (code "53") (name "PWRKEY") (class "Default")
      (node (ref "C14") (pin "2") (pinfunction "2_2") (pintype "passive"))
      (node (ref "PWR") (pin "B") (pinfunction "S_B") (pintype "passive"))
      (node (ref "PWR") (pin "B'") (pinfunction "S1_B'") (pintype "passive"))
      (node (ref "Q2") (pin "3") (pinfunction "C_3") (pintype "passive"))
      (node (ref "U3") (pin "1") (pinfunction "PWRKEY_1") (pintype "input"))
    )
    (net (code "54") (name "RESET") (class "Default")
      (node (ref "C5") (pin "2") (pinfunction "2_2") (pintype "passive"))
      (node (ref "IC1") (pin "29") (pinfunction "PC6(/RESET)_29") (pintype "bidirectional"))
      (node (ref "R4") (pin "1") (pinfunction "1_1") (pintype "passive"))
      (node (ref "RESET") (pin "A") (pinfunction "P_A") (pintype "passive"))
      (node (ref "RESET") (pin "A'") (pinfunction "P1_A'") (pintype "passive"))
      (node (ref "SPI") (pin "9") (pinfunction "9_9") (pintype "passive"))
    )
    (net (code "55") (name "RF_ANT") (class "Default")
      (node (ref "RF") (pin "D") (pinfunction "D_D") (pintype "bidirectional"))
      (node (ref "U3") (pin "60") (pinfunction "RF_ANT_60") (pintype "power_in"))
    )
    (net (code "56") (name "SCK") (class "Default")
      (node (ref "IC1") (pin "17") (pinfunction "PB5(SCK)_17") (pintype "bidirectional"))
      (node (ref "SJ2") (pin "1") (pinfunction "1_1") (pintype "passive"))
      (node (ref "SPI") (pin "5") (pinfunction "5_5") (pintype "passive"))
    )
    (net (code "57") (name "SCL") (class "Default")
      (node (ref "I2C") (pin "4") (pinfunction "4_4") (pintype "passive"))
      (node (ref "IC1") (pin "28") (pinfunction "PC5(ADC5/SCL)_28") (pintype "bidirectional"))
    )
    (net (code "58") (name "SDA") (class "Default")
      (node (ref "I2C") (pin "5") (pinfunction "5_5") (pintype "passive"))
      (node (ref "IC1") (pin "27") (pinfunction "PC4(ADC4/SDA)_27") (pintype "bidirectional"))
    )
    (net (code "59") (name "SHIELD") (class "Default")
      (node (ref "L1") (pin "2") (pinfunction "2_2") (pintype "passive"))
      (node (ref "X1") (pin "BASE@1") (pinfunction "P$1_BASE@1") (pintype "bidirectional"))
      (node (ref "X1") (pin "BASE@2") (pinfunction "P$1_BASE@2") (pintype "bidirectional"))
      (node (ref "X1") (pin "SPRT@1") (pinfunction "P$1_SPRT@1") (pintype "bidirectional"))
      (node (ref "X1") (pin "SPRT@2") (pinfunction "P$1_SPRT@2") (pintype "bidirectional"))
      (node (ref "X1") (pin "SPRT@3") (pinfunction "P$1_SPRT@3") (pintype "bidirectional"))
      (node (ref "X1") (pin "SPRT@4") (pinfunction "P$1_SPRT@4") (pintype "bidirectional"))
    )
    (net (code "60") (name "SIM7000_PWRKEY_MCU") (class "Default")
      (node (ref "R15") (pin "1") (pinfunction "1_1") (pintype "passive"))
      (node (ref "SJ2") (pin "2") (pinfunction "2_2") (pintype "passive"))
    )
    (net (code "61") (name "SIM7000_RESET") (class "Default")
      (node (ref "C15") (pin "2") (pinfunction "2_2") (pintype "passive"))
      (node (ref "Q5") (pin "3") (pinfunction "C_3") (pintype "passive"))
      (node (ref "RST") (pin "B") (pinfunction "S_B") (pintype "passive"))
      (node (ref "RST") (pin "B'") (pinfunction "S1_B'") (pintype "passive"))
      (node (ref "U3") (pin "16") (pinfunction "NRESET_16") (pintype "input"))
    )
    (net (code "62") (name "SIM7000_RESET_MCU") (class "Default")
      (node (ref "R23") (pin "1") (pinfunction "1_1") (pintype "passive"))
      (node (ref "SJ1") (pin "2") (pinfunction "2_2") (pintype "passive"))
    )
    (net (code "63") (name "SIM7000_RXD") (class "Default")
      (node (ref "U2") (pin "3") (pinfunction "A2_3") (pintype "bidirectional"))
      (node (ref "U3") (pin "10") (pinfunction "RXD_10") (pintype "input"))
    )
    (net (code "64") (name "SIM7000_TXD") (class "Default")
      (node (ref "U2") (pin "1") (pinfunction "A1_1") (pintype "bidirectional"))
      (node (ref "U3") (pin "9") (pinfunction "TXD_9") (pintype "output"))
    )
    (net (code "65") (name "SIM_CLK") (class "Default")
      (node (ref "C8") (pin "2") (pinfunction "2_2") (pintype "passive"))
      (node (ref "D1") (pin "5") (pinfunction "C4_5") (pintype "passive"))
      (node (ref "R10") (pin "2") (pinfunction "2_2") (pintype "passive"))
      (node (ref "U3") (pin "32") (pinfunction "SIM_CLK_32") (pintype "output"))
    )
    (net (code "66") (name "SIM_DATA") (class "Default")
      (node (ref "C12") (pin "2") (pinfunction "2_2") (pintype "passive"))
      (node (ref "D1") (pin "4") (pinfunction "C3_4") (pintype "passive"))
      (node (ref "R13") (pin "1") (pinfunction "1_1") (pintype "passive"))
      (node (ref "U3") (pin "31") (pinfunction "SIM_DATA_31") (pintype "output"))
    )
    (net (code "67") (name "SIM_RST") (class "Default")
      (node (ref "C9") (pin "2") (pinfunction "2_2") (pintype "passive"))
      (node (ref "D1") (pin "3") (pinfunction "C2_3") (pintype "passive"))
      (node (ref "R11") (pin "2") (pinfunction "2_2") (pintype "passive"))
      (node (ref "U3") (pin "33") (pinfunction "SIM_RST_33") (pintype "bidirectional"))
    )
    (net (code "68") (name "SIM_USB_DM_M") (class "Default")
      (node (ref "U3") (pin "28") (pinfunction "USB_DM_28") (pintype "output"))
      (node (ref "X1") (pin "D-") (pinfunction "D-_D-") (pintype "bidirectional"))
    )
    (net (code "69") (name "SIM_USB_DP_P") (class "Default")
      (node (ref "U3") (pin "27") (pinfunction "USB_DP_27") (pintype "bidirectional"))
      (node (ref "X1") (pin "D+") (pinfunction "D+_D+") (pintype "bidirectional"))
    )
    (net (code "70") (name "SIM_VDD") (class "Default")
      (node (ref "C10") (pin "1") (pinfunction "1_1") (pintype "passive"))
      (node (ref "D1") (pin "1") (pinfunction "C1_1") (pintype "passive"))
      (node (ref "U1") (pin "1") (pinfunction "VCC_1") (pintype "bidirectional"))
      (node (ref "U3") (pin "30") (pinfunction "SIM_VDD_30") (pintype "input"))
    )
    (net (code "71") (name "SS") (class "Default")
      (node (ref "IC1") (pin "14") (pinfunction "PB2(SS/OC1B)_14") (pintype "bidirectional"))
      (node (ref "SPI") (pin "8") (pinfunction "8_8") (pintype "passive"))
    )
    (net (code "72") (name "STATUS") (class "Default")
      (node (ref "R17") (pin "1") (pinfunction "1_1") (pintype "passive"))
      (node (ref "U3") (pin "66") (pinfunction "STATUS_66") (pintype "power_in"))
    )
    (net (code "73") (name "V+") (class "Default")
      (node (ref "C18") (pin "1") (pinfunction "1_1") (pintype "passive"))
      (node (ref "C23") (pin "1") (pinfunction "1_1") (pintype "passive"))
      (node (ref "C24") (pin "1") (pinfunction "1_1") (pintype "passive"))
      (node (ref "C25") (pin "1") (pinfunction "1_1") (pintype "passive"))
      (node (ref "C27") (pin "1") (pinfunction "1_1") (pintype "passive"))
      (node (ref "D2") (pin "+") (pinfunction "+_+") (pintype "passive"))
      (node (ref "D3") (pin "+") (pinfunction "+_+") (pintype "passive"))
      (node (ref "D5") (pin "C") (pinfunction "C_C") (pintype "passive"))
      (node (ref "L3") (pin "P$1") (pinfunction "1_P$1") (pintype "passive"))
      (node (ref "R1") (pin "1") (pinfunction "1_1") (pintype "passive"))
      (node (ref "R26") (pin "2") (pinfunction "2_2") (pintype "passive"))
      (node (ref "R28") (pin "1") (pinfunction "1_1") (pintype "passive"))
      (node (ref "S1") (pin "3") (pinfunction "S_3") (pintype "passive"))
      (node (ref "U3") (pin "55") (pinfunction "VBAT_55") (pintype "power_in"))
      (node (ref "U3") (pin "56") (pinfunction "VBAT_56") (pintype "power_in"))
      (node (ref "U3") (pin "57") (pinfunction "VBAT_57") (pintype "power_in"))
      (node (ref "U5") (pin "1") (pinfunction "IN_1") (pintype "power_in"))
      (node (ref "U6") (pin "3") (pinfunction "VIN_3") (pintype "bidirectional"))
    )
    (net (code "74") (name "VBUS") (class "Default")
      (node (ref "C17") (pin "1") (pinfunction "1_1") (pintype "passive"))
      (node (ref "D4") (pin "A") (pinfunction "A_A") (pintype "passive"))
      (node (ref "L2") (pin "1") (pinfunction "1_1") (pintype "passive"))
      (node (ref "PGM") (pin "2") (pinfunction "2_2") (pintype "passive"))
      (node (ref "U3") (pin "24") (pinfunction "USB_VBUS_24") (pintype "output"))
      (node (ref "U4") (pin "4") (pinfunction "VDD_4") (pintype "power_in"))
    )
    (net (code "75") (name "VDD_EXT") (class "Default")
      (node (ref "C11") (pin "2") (pinfunction "2_2") (pintype "passive"))
      (node (ref "U2") (pin "10") (pinfunction "OE_10") (pintype "bidirectional"))
      (node (ref "U2") (pin "2") (pinfunction "VCCA_2") (pintype "bidirectional"))
      (node (ref "U3") (pin "15") (pinfunction "VDD_EXT_15") (pintype "output"))
    )
    (net (code "76") (name "unconnected-(D1-C5-Pad6)") (class "Default")
      (node (ref "D1") (pin "6") (pinfunction "C5_6") (pintype "passive"))
    )
    (net (code "77") (name "unconnected-(IC1-ADC6-Pad19)") (class "Default")
      (node (ref "IC1") (pin "19") (pinfunction "ADC6_19") (pintype "bidirectional"))
    )
    (net (code "78") (name "unconnected-(IC1-ADC7-Pad22)") (class "Default")
      (node (ref "IC1") (pin "22") (pinfunction "ADC7_22") (pintype "bidirectional"))
    )
    (net (code "79") (name "unconnected-(IC1-PB1(OC1A)-Pad13)") (class "Default")
      (node (ref "IC1") (pin "13") (pinfunction "PB1(OC1A)_13") (pintype "bidirectional"))
    )
    (net (code "80") (name "unconnected-(IC1-PC2(ADC2)-Pad25)") (class "Default")
      (node (ref "IC1") (pin "25") (pinfunction "PC2(ADC2)_25") (pintype "bidirectional"))
    )
    (net (code "81") (name "unconnected-(IC1-PC3(ADC3)-Pad26)") (class "Default")
      (node (ref "IC1") (pin "26") (pinfunction "PC3(ADC3)_26") (pintype "bidirectional"))
    )
    (net (code "82") (name "unconnected-(PGM-Pad3)") (class "Default")
      (node (ref "PGM") (pin "3") (pinfunction "3_3") (pintype "passive"))
    )
    (net (code "83") (name "unconnected-(U1-VPP-Pad6)") (class "Default")
      (node (ref "U1") (pin "6") (pinfunction "VPP_6") (pintype "bidirectional"))
    )
    (net (code "84") (name "unconnected-(U2-A3-Pad4)") (class "Default")
      (node (ref "U2") (pin "4") (pinfunction "A3_4") (pintype "bidirectional"))
    )
    (net (code "85") (name "unconnected-(U2-A4-Pad5)") (class "Default")
      (node (ref "U2") (pin "5") (pinfunction "A4_5") (pintype "bidirectional"))
    )
    (net (code "86") (name "unconnected-(U2-A5-Pad6)") (class "Default")
      (node (ref "U2") (pin "6") (pinfunction "A5_6") (pintype "bidirectional"))
    )
    (net (code "87") (name "unconnected-(U2-A6-Pad7)") (class "Default")
      (node (ref "U2") (pin "7") (pinfunction "A6_7") (pintype "bidirectional"))
    )
    (net (code "88") (name "unconnected-(U2-A7-Pad8)") (class "Default")
      (node (ref "U2") (pin "8") (pinfunction "A7_8") (pintype "bidirectional"))
    )
    (net (code "89") (name "unconnected-(U2-B3-Pad17)") (class "Default")
      (node (ref "U2") (pin "17") (pinfunction "B3_17") (pintype "bidirectional"))
    )
    (net (code "90") (name "unconnected-(U2-B4-Pad16)") (class "Default")
      (node (ref "U2") (pin "16") (pinfunction "B4_16") (pintype "bidirectional"))
    )
    (net (code "91") (name "unconnected-(U2-B5-Pad15)") (class "Default")
      (node (ref "U2") (pin "15") (pinfunction "B5_15") (pintype "bidirectional"))
    )
    (net (code "92") (name "unconnected-(U2-B6-Pad14)") (class "Default")
      (node (ref "U2") (pin "14") (pinfunction "B6_14") (pintype "bidirectional"))
    )
    (net (code "93") (name "unconnected-(U2-B7-Pad13)") (class "Default")
      (node (ref "U2") (pin "13") (pinfunction "B7_13") (pintype "bidirectional"))
    )
    (net (code "94") (name "unconnected-(U3-ADC-Pad25)") (class "Default")
      (node (ref "U3") (pin "25") (pinfunction "ADC_25") (pintype "input"))
    )
    (net (code "95") (name "unconnected-(U3-BOOT_CFG-Pad6)") (class "Default")
      (node (ref "U3") (pin "6") (pinfunction "BOOT_CFG_6") (pintype "output"))
    )
    (net (code "96") (name "unconnected-(U3-CTS-Pad7)") (class "Default")
      (node (ref "U3") (pin "7") (pinfunction "CTS_7") (pintype "output"))
    )
    (net (code "97") (name "unconnected-(U3-DCD-Pad5)") (class "Default")
      (node (ref "U3") (pin "5") (pinfunction "DCD_5") (pintype "output"))
    )
    (net (code "98") (name "unconnected-(U3-DTR-Pad3)") (class "Default")
      (node (ref "U3") (pin "3") (pinfunction "DTR_3") (pintype "input"))
    )
    (net (code "99") (name "unconnected-(U3-GPIO0-Pad50)") (class "Default")
      (node (ref "U3") (pin "50") (pinfunction "GPIO0_50") (pintype "bidirectional"))
    )
    (net (code "100") (name "unconnected-(U3-GPIO1-Pad49)") (class "Default")
      (node (ref "U3") (pin "49") (pinfunction "GPIO1_49") (pintype "bidirectional"))
    )
    (net (code "101") (name "unconnected-(U3-GPIO4-Pad48)") (class "Default")
      (node (ref "U3") (pin "48") (pinfunction "GPIO4_48") (pintype "input"))
    )
    (net (code "102") (name "unconnected-(U3-MDM_LOG_TX-Pad23)") (class "Default")
      (node (ref "U3") (pin "23") (pinfunction "MDM_LOG_TX_23") (pintype "input"))
    )
    (net (code "103") (name "unconnected-(U3-NC-Pad19)") (class "Default")
      (node (ref "U3") (pin "19") (pinfunction "NC_19") (pintype "input"))
    )
    (net (code "104") (name "unconnected-(U3-NC-Pad20)") (class "Default")
      (node (ref "U3") (pin "20") (pinfunction "NC_20") (pintype "output"))
    )
    (net (code "105") (name "unconnected-(U3-NC-Pad21)") (class "Default")
      (node (ref "U3") (pin "21") (pinfunction "NC_21") (pintype "output"))
    )
    (net (code "106") (name "unconnected-(U3-NC-Pad22)") (class "Default")
      (node (ref "U3") (pin "22") (pinfunction "NC_22") (pintype "input"))
    )
    (net (code "107") (name "unconnected-(U3-NC-Pad26)") (class "Default")
      (node (ref "U3") (pin "26") (pinfunction "NC_26") (pintype "output"))
    )
    (net (code "108") (name "unconnected-(U3-NC-Pad35)") (class "Default")
      (node (ref "U3") (pin "35") (pinfunction "NC_35") (pintype "input"))
    )
    (net (code "109") (name "unconnected-(U3-NC-Pad36)") (class "Default")
      (node (ref "U3") (pin "36") (pinfunction "NC_36") (pintype "output"))
    )
    (net (code "110") (name "unconnected-(U3-NC-Pad40)") (class "Default")
      (node (ref "U3") (pin "40") (pinfunction "NC_40") (pintype "output"))
    )
    (net (code "111") (name "unconnected-(U3-NC-Pad41)") (class "Default")
      (node (ref "U3") (pin "41") (pinfunction "NC_41") (pintype "output"))
    )
    (net (code "112") (name "unconnected-(U3-NC-Pad42)") (class "Default")
      (node (ref "U3") (pin "42") (pinfunction "NC_42") (pintype "output"))
    )
    (net (code "113") (name "unconnected-(U3-NC-Pad43)") (class "Default")
      (node (ref "U3") (pin "43") (pinfunction "NC_43") (pintype "output"))
    )
    (net (code "114") (name "unconnected-(U3-NC-Pad44)") (class "Default")
      (node (ref "U3") (pin "44") (pinfunction "NC_44") (pintype "output"))
    )
    (net (code "115") (name "unconnected-(U3-NC-Pad47)") (class "Default")
      (node (ref "U3") (pin "47") (pinfunction "NC_47") (pintype "input"))
    )
    (net (code "116") (name "unconnected-(U3-NC-Pad51)") (class "Default")
      (node (ref "U3") (pin "51") (pinfunction "NC_51") (pintype "bidirectional"))
    )
    (net (code "117") (name "unconnected-(U3-PCM_CLK-Pad11)") (class "Default")
      (node (ref "U3") (pin "11") (pinfunction "PCM_CLK_11") (pintype "output"))
    )
    (net (code "118") (name "unconnected-(U3-PCM_DIN-Pad13)") (class "Default")
      (node (ref "U3") (pin "13") (pinfunction "PCM_DIN_13") (pintype "output"))
    )
    (net (code "119") (name "unconnected-(U3-PCM_DOUT-Pad14)") (class "Default")
      (node (ref "U3") (pin "14") (pinfunction "PCM_DOUT_14") (pintype "output"))
    )
    (net (code "120") (name "unconnected-(U3-PCM_SYNC-Pad12)") (class "Default")
      (node (ref "U3") (pin "12") (pinfunction "PCM_SYNC_12") (pintype "bidirectional"))
    )
    (net (code "121") (name "unconnected-(U3-RI-Pad4)") (class "Default")
      (node (ref "U3") (pin "4") (pinfunction "RI_4") (pintype "output"))
    )
    (net (code "122") (name "unconnected-(U3-RTS-Pad8)") (class "Default")
      (node (ref "U3") (pin "8") (pinfunction "RTS_8") (pintype "input"))
    )
    (net (code "123") (name "unconnected-(U3-SCL-Pad38)") (class "Default")
      (node (ref "U3") (pin "38") (pinfunction "SCL_38") (pintype "output"))
    )
    (net (code "124") (name "unconnected-(U3-SDA-Pad37)") (class "Default")
      (node (ref "U3") (pin "37") (pinfunction "SDA_37") (pintype "bidirectional"))
    )
    (net (code "125") (name "unconnected-(U3-SIM_DET-Pad34)") (class "Default")
      (node (ref "U3") (pin "34") (pinfunction "SIM_DET_34") (pintype "bidirectional"))
    )
    (net (code "126") (name "unconnected-(U5-P4-Pad4)") (class "Default")
      (node (ref "U5") (pin "4") (pinfunction "P4_4") (pintype "bidirectional"))
    )
    (net (code "127") (name "unconnected-(U6-RSET-Pad6)") (class "Default")
      (node (ref "U6") (pin "6") (pinfunction "RSET_6") (pintype "bidirectional"))
    )
    (net (code "128") (name "unconnected-(X1-PadID)") (class "Default")
      (node (ref "X1") (pin "ID") (pinfunction "ID_ID") (pintype "bidirectional"))
    )
  )
)
